# 5V-REG.net
KiCad netlist of a schematic drawn in Altium Designer
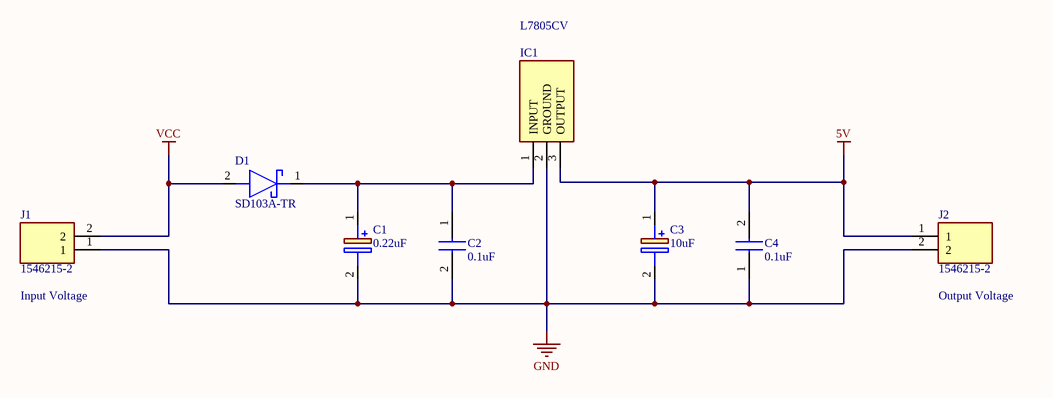
[diagram p0: 5V-REG.SchDoc]

(export (version "E")
  (design (tool "Eeschema 10.0.6"))
  (components
    (comp (ref "C1")
      (value "0.22uF")
      (footprint "SamacSys:CAPPRD200W52D500H1250")
      (description "Capacitor Polarised")
      (fields
        (field (name "MANUFACTURER_PART_NUMBER") "860010772002")
        (field (name "MOUSER PART NUMBER") "710-860010772002")
      )
      (libsource (lib "*") (part "860010772002"))
    )
    (comp (ref "C2")
      (value "0.1uF")
      (footprint "SamacSys:RDER71E104K0P1H03B")
      (description "Capacitor")
      (fields
        (field (name "MANUFACTURER_PART_NUMBER") "RDER71E104K0P1H03B")
        (field (name "MOUSER PART NUMBER") "81-RDER71E104K0P1H3B")
      )
      (libsource (lib "*") (part "RDER71E104K0P1H03B"))
    )
    (comp (ref "C3")
      (value "10uF")
      (footprint "SamacSys:CAPPRD200W55D500H1250")
      (description "Capacitor Polarised")
      (fields
        (field (name "MANUFACTURER_PART_NUMBER") "EEU-FR1H100")
        (field (name "MOUSER PART NUMBER") "667-EEU-FR1H100")
      )
      (libsource (lib "*") (part "EEU-FR1H100"))
    )
    (comp (ref "C4")
      (value "0.1uF")
      (footprint "SamacSys:RDER71E104K0P1H03B")
      (description "Capacitor")
      (fields
        (field (name "MANUFACTURER_PART_NUMBER") "RDER71E104K0P1H03B")
        (field (name "MOUSER PART NUMBER") "81-RDER71E104K0P1H3B")
      )
      (libsource (lib "*") (part "RDER71E104K0P1H03B"))
    )
    (comp (ref "D1")
      (value "SD103A-TR")
      (footprint "SamacSys:DIOAD950W60L350D150")
      (description "Schottky Diode")
      (fields (field (name "MOUSER PART NUMBER") "625-SD103A"))
      (libsource (lib "*") (part "SD103A-TR"))
    )
    (comp (ref "IC1")
      (value "L7805CV")
      (footprint "SamacSys:TO255P460X1020X2008-3P")
      (description "Integrated Circuit")
      (fields (field (name "MOUSER PART NUMBER") "511-L7805CV"))
      (libsource (lib "*") (part "L7805CV"))
    )
    (comp (ref "J1")
      (value "1546215-2")
      (footprint "SamacSys:15462152")
      (description "Connector")
      (fields (field (name "MOUSER PART NUMBER") "571-1546215-2"))
      (libsource (lib "") (part "1546215-2_1"))
    )
    (comp (ref "J2")
      (value "1546215-2")
      (footprint "SamacSys:15462152")
      (description "Connector")
      (fields (field (name "MOUSER PART NUMBER") "571-1546215-2"))
      (libsource (lib "*") (part "1546215-2"))
    )
  )
  (nets
    (net (code "1") (name "5V") (class "Default")
      (node (ref "C3") (pin "1") (pinfunction "+_1") (pintype "power_in"))
      (node (ref "C4") (pin "2") (pinfunction "2_2") (pintype "passive"))
      (node (ref "IC1") (pin "3") (pinfunction "OUTPUT_3") (pintype "passive"))
      (node (ref "J2") (pin "1") (pinfunction "1_1") (pintype "passive"))
    )
    (net (code "2") (name "GND") (class "Default")
      (node (ref "C1") (pin "2") (pinfunction "-_2") (pintype "passive"))
      (node (ref "C2") (pin "2") (pinfunction "2_2") (pintype "passive"))
      (node (ref "C3") (pin "2") (pinfunction "-_2") (pintype "power_in"))
      (node (ref "C4") (pin "1") (pinfunction "1_1") (pintype "passive"))
      (node (ref "IC1") (pin "2") (pinfunction "GROUND_2") (pintype "passive"))
      (node (ref "J1") (pin "1") (pinfunction "1_1") (pintype "passive"))
      (node (ref "J2") (pin "2") (pinfunction "2_2") (pintype "passive"))
    )
    (net (code "3") (name "Net-(C1-+)") (class "Default")
      (node (ref "C1") (pin "1") (pinfunction "+_1") (pintype "passive"))
      (node (ref "C2") (pin "1") (pinfunction "1_1") (pintype "passive"))
      (node (ref "D1") (pin "1") (pinfunction "K_1") (pintype "passive"))
      (node (ref "IC1") (pin "1") (pinfunction "INPUT_1") (pintype "passive"))
    )
    (net (code "4") (name "VCC") (class "Default")
      (node (ref "D1") (pin "2") (pinfunction "A_2") (pintype "passive"))
      (node (ref "J1") (pin "2") (pinfunction "2_2") (pintype "passive"))
    )
  )
)
